# MainSheet.net
KiCad netlist of a schematic drawn in Altium Designer
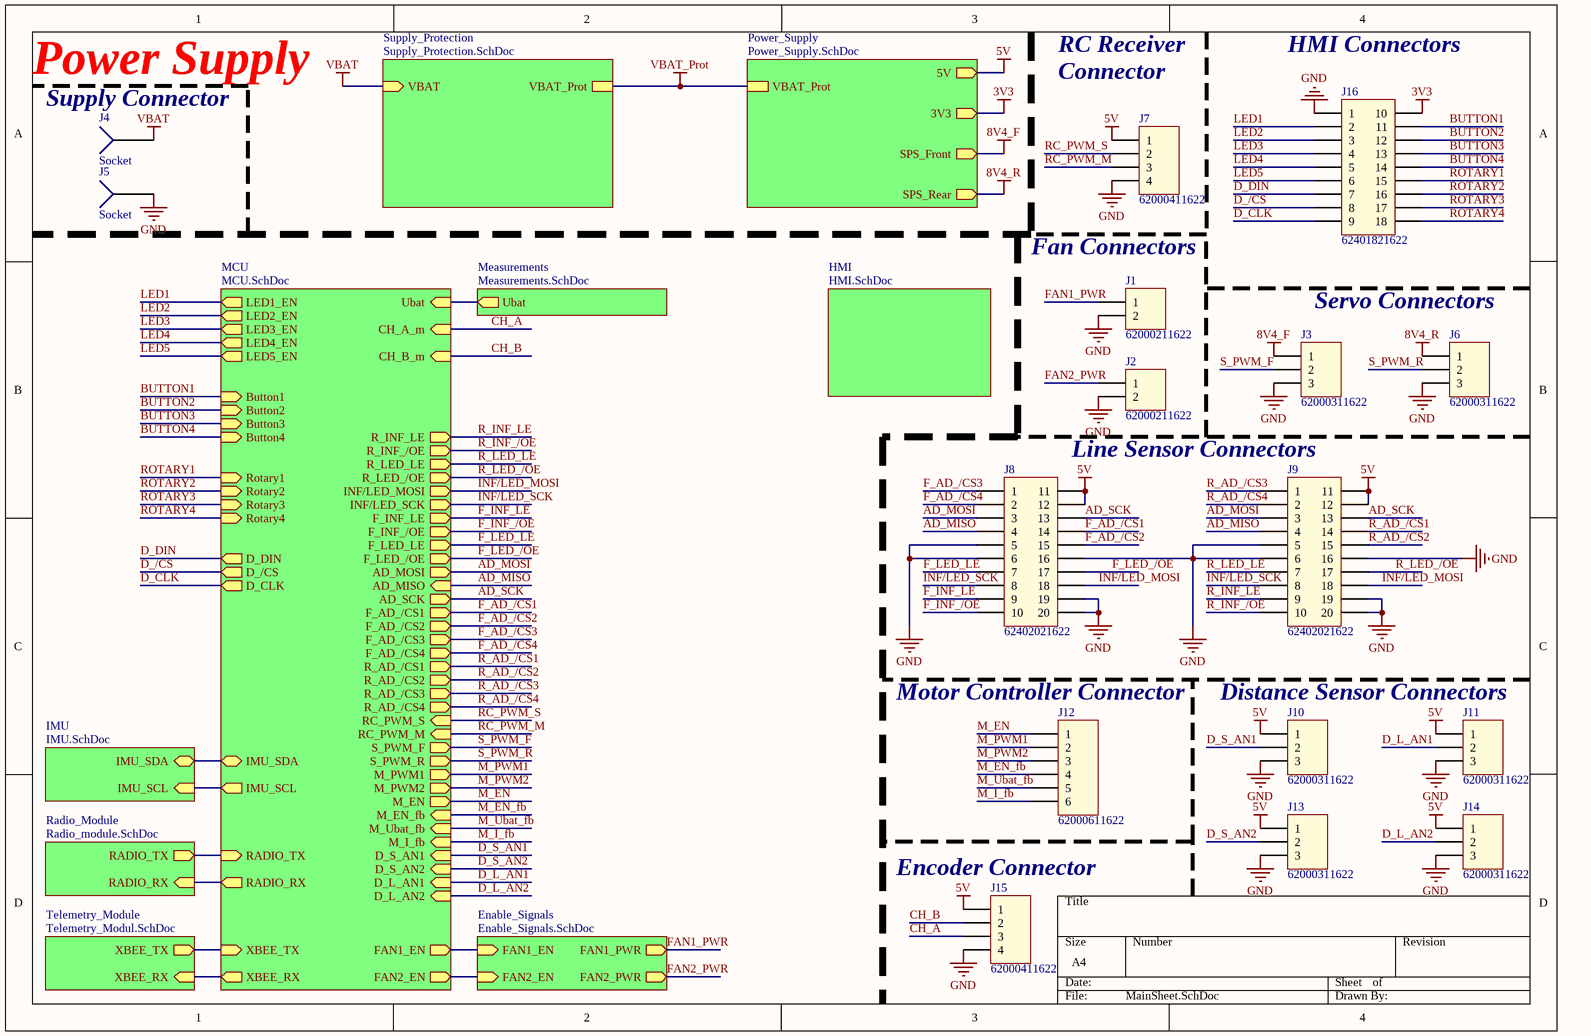
[diagram p0: MainSheet.SchDoc]

(export (version "E")
  (design (tool "Eeschema 10.0.6"))
  (components
    (comp (ref "J1")
      (value "62000211622")
      (footprint "62000211622")
      (description "WR-WTB 2.00mm Male Vertical Shrouded Header, 2p")
      (fields (field (name "PUBLISHER") "Wurth Elektronik"))
      (libsource (lib "Components") (part "62000211622"))
    )
    (comp (ref "J2")
      (value "62000211622")
      (footprint "62000211622")
      (description "WR-WTB 2.00mm Male Vertical Shrouded Header, 2p")
      (fields (field (name "PUBLISHER") "Wurth Elektronik"))
      (libsource (lib "Components") (part "62000211622"))
    )
    (comp (ref "J3")
      (value "62000311622")
      (footprint "62000311622")
      (description "WR-WTB 2.00mm Male Vertical Shrouded Header, 3p")
      (fields (field (name "PUBLISHER") "Wurth Elektronik"))
      (libsource (lib "Components") (part "62000311622"))
    )
    (comp (ref "J4")
      (value "Socket")
      (footprint "TAB 6.35MM x 0.81MM")
      (fields (field (name "PART NUMBER") "1217861-1 TERMINAL"))
      (libsource (lib "Components") (part "Socket"))
    )
    (comp (ref "J5")
      (value "Socket")
      (footprint "TAB 6.35MM x 0.81MM")
      (fields (field (name "PART NUMBER") "1217861-1 TERMINAL"))
      (libsource (lib "Components") (part "Socket"))
    )
    (comp (ref "J6")
      (value "62000311622")
      (footprint "62000311622")
      (description "WR-WTB 2.00mm Male Vertical Shrouded Header, 3p")
      (fields (field (name "PUBLISHER") "Wurth Elektronik"))
      (libsource (lib "Components") (part "62000311622"))
    )
    (comp (ref "J7")
      (value "62000411622")
      (footprint "62000411622")
      (description "WR-WTB 2.00mm Male Vertical Shrouded Header, 4p")
      (fields (field (name "PUBLISHER") "Wurth Elektronik"))
      (libsource (lib "Components") (part "62000411622"))
    )
    (comp (ref "J8")
      (value "62402021622")
      (footprint "62402021622")
      (description "WR-WTB 2.00mm Male Dual Row Vertical Shrouded Header with positive locking, 20p")
      (fields (field (name "PUBLISHER") "Wurth Elektronik"))
      (libsource (lib "Components") (part "62402021622"))
    )
    (comp (ref "J9")
      (value "62402021622")
      (footprint "62402021622")
      (description "WR-WTB 2.00mm Male Dual Row Vertical Shrouded Header with positive locking, 20p")
      (fields (field (name "PUBLISHER") "Wurth Elektronik"))
      (libsource (lib "Components") (part "62402021622"))
    )
    (comp (ref "J10")
      (value "62000311622")
      (footprint "62000311622")
      (description "WR-WTB 2.00mm Male Vertical Shrouded Header, 3p")
      (fields (field (name "PUBLISHER") "Wurth Elektronik"))
      (libsource (lib "Components") (part "62000311622"))
    )
    (comp (ref "J11")
      (value "62000311622")
      (footprint "62000311622")
      (description "WR-WTB 2.00mm Male Vertical Shrouded Header, 3p")
      (fields (field (name "PUBLISHER") "Wurth Elektronik"))
      (libsource (lib "Components") (part "62000311622"))
    )
    (comp (ref "J12")
      (value "62000611622")
      (footprint "62000611622")
      (description "WR-WTB 2.00mm Male Vertical Shrouded Header, 6p")
      (fields (field (name "PUBLISHER") "Wurth Elektronik"))
      (libsource (lib "Components") (part "62000611622"))
    )
    (comp (ref "J13")
      (value "62000311622")
      (footprint "62000311622")
      (description "WR-WTB 2.00mm Male Vertical Shrouded Header, 3p")
      (fields (field (name "PUBLISHER") "Wurth Elektronik"))
      (libsource (lib "Components") (part "62000311622"))
    )
    (comp (ref "J14")
      (value "62000311622")
      (footprint "62000311622")
      (description "WR-WTB 2.00mm Male Vertical Shrouded Header, 3p")
      (fields (field (name "PUBLISHER") "Wurth Elektronik"))
      (libsource (lib "Components") (part "62000311622"))
    )
    (comp (ref "J15")
      (value "62000411622")
      (footprint "62000411622")
      (description "WR-WTB 2.00mm Male Vertical Shrouded Header, 4p")
      (fields (field (name "PUBLISHER") "Wurth Elektronik"))
      (libsource (lib "Components") (part "62000411622"))
    )
    (comp (ref "J16")
      (value "62401821622")
      (footprint "62401821622")
      (description "WR-WTB 2.00mm Male Dual Row Vertical Shrouded Header with positive locking, 18p")
      (fields (field (name "PUBLISHER") "Wurth Elektronik"))
      (libsource (lib "Components") (part "62401821622"))
    )
  )
  (nets
    (net (code "1") (name "/AD_MISO") (class "Default")
      (node (ref "J8") (pin "4") (pinfunction "4_4") (pintype "passive"))
      (node (ref "J9") (pin "4") (pinfunction "4_4") (pintype "passive"))
    )
    (net (code "2") (name "/AD_MOSI") (class "Default")
      (node (ref "J8") (pin "3") (pinfunction "3_3") (pintype "passive"))
      (node (ref "J9") (pin "3") (pinfunction "3_3") (pintype "passive"))
    )
    (net (code "3") (name "/AD_SCK") (class "Default")
      (node (ref "J8") (pin "13") (pinfunction "13_13") (pintype "passive"))
      (node (ref "J9") (pin "13") (pinfunction "13_13") (pintype "passive"))
    )
    (net (code "4") (name "/BUTTON1") (class "Default")
      (node (ref "J16") (pin "11") (pinfunction "11_11") (pintype "passive"))
    )
    (net (code "5") (name "/BUTTON2") (class "Default")
      (node (ref "J16") (pin "12") (pinfunction "12_12") (pintype "passive"))
    )
    (net (code "6") (name "/BUTTON3") (class "Default")
      (node (ref "J16") (pin "13") (pinfunction "13_13") (pintype "passive"))
    )
    (net (code "7") (name "/BUTTON4") (class "Default")
      (node (ref "J16") (pin "14") (pinfunction "14_14") (pintype "passive"))
    )
    (net (code "8") (name "/CH_A") (class "Default")
      (node (ref "J15") (pin "3") (pinfunction "3_3") (pintype "passive"))
    )
    (net (code "9") (name "/CH_B") (class "Default")
      (node (ref "J15") (pin "2") (pinfunction "2_2") (pintype "passive"))
    )
    (net (code "10") (name "/D_CLK") (class "Default")
      (node (ref "J16") (pin "9") (pinfunction "9_9") (pintype "passive"))
    )
    (net (code "11") (name "/D_DIN") (class "Default")
      (node (ref "J16") (pin "7") (pinfunction "7_7") (pintype "passive"))
    )
    (net (code "12") (name "/D_L_AN1") (class "Default")
      (node (ref "J11") (pin "2") (pinfunction "2_2") (pintype "passive"))
    )
    (net (code "13") (name "/D_L_AN2") (class "Default")
      (node (ref "J14") (pin "2") (pinfunction "2_2") (pintype "passive"))
    )
    (net (code "14") (name "/D_S_AN1") (class "Default")
      (node (ref "J10") (pin "2") (pinfunction "2_2") (pintype "passive"))
    )
    (net (code "15") (name "/D_S_AN2") (class "Default")
      (node (ref "J13") (pin "2") (pinfunction "2_2") (pintype "passive"))
    )
    (net (code "16") (name "/D_{slash}CS") (class "Default")
      (node (ref "J16") (pin "8") (pinfunction "8_8") (pintype "passive"))
    )
    (net (code "18") (name "/FAN1_PWR") (class "Default")
      (node (ref "J1") (pin "1") (pinfunction "1_1") (pintype "passive"))
    )
    (net (code "20") (name "/FAN2_PWR") (class "Default")
      (node (ref "J2") (pin "1") (pinfunction "1_1") (pintype "passive"))
    )
    (net (code "21") (name "/F_AD_{slash}CS1") (class "Default")
      (node (ref "J8") (pin "14") (pinfunction "14_14") (pintype "passive"))
    )
    (net (code "22") (name "/F_AD_{slash}CS2") (class "Default")
      (node (ref "J8") (pin "15") (pinfunction "15_15") (pintype "passive"))
    )
    (net (code "23") (name "/F_AD_{slash}CS3") (class "Default")
      (node (ref "J8") (pin "1") (pinfunction "1_1") (pintype "passive"))
    )
    (net (code "24") (name "/F_AD_{slash}CS4") (class "Default")
      (node (ref "J8") (pin "2") (pinfunction "2_2") (pintype "passive"))
    )
    (net (code "25") (name "/F_INF_LE") (class "Default")
      (node (ref "J8") (pin "9") (pinfunction "9_9") (pintype "passive"))
    )
    (net (code "26") (name "/F_INF_{slash}OE") (class "Default")
      (node (ref "J8") (pin "10") (pinfunction "10_10") (pintype "passive"))
    )
    (net (code "27") (name "/F_LED_LE") (class "Default")
      (node (ref "J8") (pin "7") (pinfunction "7_7") (pintype "passive"))
    )
    (net (code "28") (name "/F_LED_{slash}OE") (class "Default")
      (node (ref "J8") (pin "17") (pinfunction "17_17") (pintype "passive"))
    )
    (net (code "31") (name "/INF{slash}LED_MOSI") (class "Default")
      (node (ref "J8") (pin "18") (pinfunction "18_18") (pintype "passive"))
      (node (ref "J9") (pin "18") (pinfunction "18_18") (pintype "passive"))
    )
    (net (code "32") (name "/INF{slash}LED_SCK") (class "Default")
      (node (ref "J8") (pin "8") (pinfunction "8_8") (pintype "passive"))
      (node (ref "J9") (pin "8") (pinfunction "8_8") (pintype "passive"))
    )
    (net (code "33") (name "/LED1") (class "Default")
      (node (ref "J16") (pin "2") (pinfunction "2_2") (pintype "passive"))
    )
    (net (code "34") (name "/LED2") (class "Default")
      (node (ref "J16") (pin "3") (pinfunction "3_3") (pintype "passive"))
    )
    (net (code "35") (name "/LED3") (class "Default")
      (node (ref "J16") (pin "4") (pinfunction "4_4") (pintype "passive"))
    )
    (net (code "36") (name "/LED4") (class "Default")
      (node (ref "J16") (pin "5") (pinfunction "5_5") (pintype "passive"))
    )
    (net (code "37") (name "/LED5") (class "Default")
      (node (ref "J16") (pin "6") (pinfunction "6_6") (pintype "passive"))
    )
    (net (code "38") (name "/M_EN") (class "Default")
      (node (ref "J12") (pin "1") (pinfunction "1_1") (pintype "passive"))
    )
    (net (code "39") (name "/M_EN_fb") (class "Default")
      (node (ref "J12") (pin "4") (pinfunction "4_4") (pintype "passive"))
    )
    (net (code "40") (name "/M_I_fb") (class "Default")
      (node (ref "J12") (pin "6") (pinfunction "6_6") (pintype "passive"))
    )
    (net (code "41") (name "/M_PWM1") (class "Default")
      (node (ref "J12") (pin "2") (pinfunction "2_2") (pintype "passive"))
    )
    (net (code "42") (name "/M_PWM2") (class "Default")
      (node (ref "J12") (pin "3") (pinfunction "3_3") (pintype "passive"))
    )
    (net (code "43") (name "/M_Ubat_fb") (class "Default")
      (node (ref "J12") (pin "5") (pinfunction "5_5") (pintype "passive"))
    )
    (net (code "46") (name "/RC_PWM_M") (class "Default")
      (node (ref "J7") (pin "3") (pinfunction "3_3") (pintype "passive"))
    )
    (net (code "47") (name "/RC_PWM_S") (class "Default")
      (node (ref "J7") (pin "2") (pinfunction "2_2") (pintype "passive"))
    )
    (net (code "48") (name "/ROTARY1") (class "Default")
      (node (ref "J16") (pin "15") (pinfunction "15_15") (pintype "passive"))
    )
    (net (code "49") (name "/ROTARY2") (class "Default")
      (node (ref "J16") (pin "16") (pinfunction "16_16") (pintype "passive"))
    )
    (net (code "50") (name "/ROTARY3") (class "Default")
      (node (ref "J16") (pin "17") (pinfunction "17_17") (pintype "passive"))
    )
    (net (code "51") (name "/ROTARY4") (class "Default")
      (node (ref "J16") (pin "18") (pinfunction "18_18") (pintype "passive"))
    )
    (net (code "52") (name "/R_AD_{slash}CS1") (class "Default")
      (node (ref "J9") (pin "14") (pinfunction "14_14") (pintype "passive"))
    )
    (net (code "53") (name "/R_AD_{slash}CS2") (class "Default")
      (node (ref "J9") (pin "15") (pinfunction "15_15") (pintype "passive"))
    )
    (net (code "54") (name "/R_AD_{slash}CS3") (class "Default")
      (node (ref "J9") (pin "1") (pinfunction "1_1") (pintype "passive"))
    )
    (net (code "55") (name "/R_AD_{slash}CS4") (class "Default")
      (node (ref "J9") (pin "2") (pinfunction "2_2") (pintype "passive"))
    )
    (net (code "56") (name "/R_INF_LE") (class "Default")
      (node (ref "J9") (pin "9") (pinfunction "9_9") (pintype "passive"))
    )
    (net (code "57") (name "/R_INF_{slash}OE") (class "Default")
      (node (ref "J9") (pin "10") (pinfunction "10_10") (pintype "passive"))
    )
    (net (code "58") (name "/R_LED_LE") (class "Default")
      (node (ref "J9") (pin "7") (pinfunction "7_7") (pintype "passive"))
    )
    (net (code "59") (name "/R_LED_{slash}OE") (class "Default")
      (node (ref "J9") (pin "17") (pinfunction "17_17") (pintype "passive"))
    )
    (net (code "60") (name "/S_PWM_F") (class "Default")
      (node (ref "J3") (pin "2") (pinfunction "2_2") (pintype "passive"))
    )
    (net (code "61") (name "/S_PWM_R") (class "Default")
      (node (ref "J6") (pin "2") (pinfunction "2_2") (pintype "passive"))
    )
    (net (code "65") (name "3V3") (class "Default")
      (node (ref "J16") (pin "10") (pinfunction "10_10") (pintype "passive"))
    )
    (net (code "66") (name "5V") (class "Default")
      (node (ref "J10") (pin "1") (pinfunction "1_1") (pintype "passive"))
      (node (ref "J11") (pin "1") (pinfunction "1_1") (pintype "passive"))
      (node (ref "J13") (pin "1") (pinfunction "1_1") (pintype "passive"))
      (node (ref "J14") (pin "1") (pinfunction "1_1") (pintype "passive"))
      (node (ref "J15") (pin "1") (pinfunction "1_1") (pintype "passive"))
      (node (ref "J7") (pin "1") (pinfunction "1_1") (pintype "passive"))
      (node (ref "J8") (pin "11") (pinfunction "11_11") (pintype "passive"))
      (node (ref "J8") (pin "12") (pinfunction "12_12") (pintype "passive"))
      (node (ref "J9") (pin "11") (pinfunction "11_11") (pintype "passive"))
      (node (ref "J9") (pin "12") (pinfunction "12_12") (pintype "passive"))
    )
    (net (code "67") (name "8V4_F") (class "Default")
      (node (ref "J3") (pin "1") (pinfunction "1_1") (pintype "passive"))
    )
    (net (code "68") (name "8V4_R") (class "Default")
      (node (ref "J6") (pin "1") (pinfunction "1_1") (pintype "passive"))
    )
    (net (code "69") (name "GND") (class "Default")
      (node (ref "J1") (pin "2") (pinfunction "2_2") (pintype "passive"))
      (node (ref "J10") (pin "3") (pinfunction "3_3") (pintype "passive"))
      (node (ref "J11") (pin "3") (pinfunction "3_3") (pintype "passive"))
      (node (ref "J13") (pin "3") (pinfunction "3_3") (pintype "passive"))
      (node (ref "J14") (pin "3") (pinfunction "3_3") (pintype "passive"))
      (node (ref "J15") (pin "4") (pinfunction "4_4") (pintype "passive"))
      (node (ref "J16") (pin "1") (pinfunction "1_1") (pintype "passive"))
      (node (ref "J2") (pin "2") (pinfunction "2_2") (pintype "passive"))
      (node (ref "J3") (pin "3") (pinfunction "3_3") (pintype "passive"))
      (node (ref "J5") (pin "1") (pinfunction "1_1") (pintype "passive"))
      (node (ref "J6") (pin "3") (pinfunction "3_3") (pintype "passive"))
      (node (ref "J7") (pin "4") (pinfunction "4_4") (pintype "passive"))
      (node (ref "J8") (pin "16") (pinfunction "16_16") (pintype "passive"))
      (node (ref "J8") (pin "19") (pinfunction "19_19") (pintype "passive"))
      (node (ref "J8") (pin "20") (pinfunction "20_20") (pintype "passive"))
      (node (ref "J8") (pin "5") (pinfunction "5_5") (pintype "passive"))
      (node (ref "J8") (pin "6") (pinfunction "6_6") (pintype "passive"))
      (node (ref "J9") (pin "16") (pinfunction "16_16") (pintype "passive"))
      (node (ref "J9") (pin "19") (pinfunction "19_19") (pintype "passive"))
      (node (ref "J9") (pin "20") (pinfunction "20_20") (pintype "passive"))
      (node (ref "J9") (pin "5") (pinfunction "5_5") (pintype "passive"))
      (node (ref "J9") (pin "6") (pinfunction "6_6") (pintype "passive"))
    )
    (net (code "70") (name "VBAT") (class "Default")
      (node (ref "J4") (pin "1") (pinfunction "1_1") (pintype "passive"))
    )
  )
)
